# 05_Ethernet.net
KiCad netlist of a schematic drawn in Altium Designer
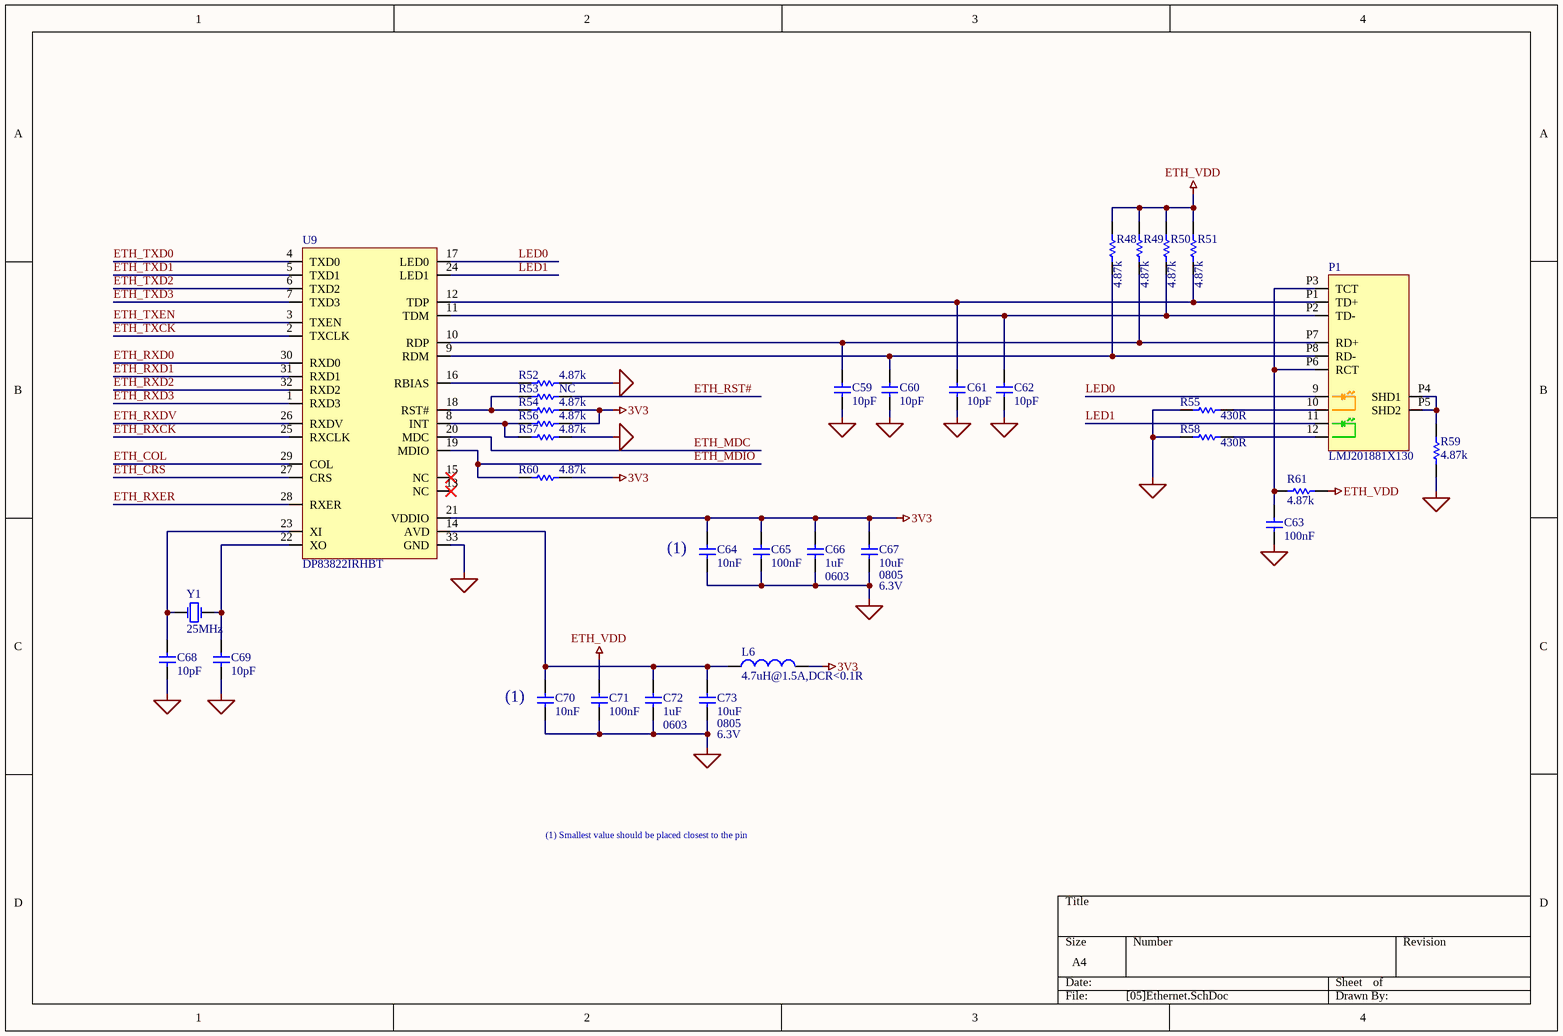
[diagram p0: [05]Ethernet.SchDoc]

(export (version "E")
  (design (tool "Eeschema 10.0.6"))
  (components
    (comp (ref "C59")
      (value "10pF")
      (footprint "C0402")
      (description "SMD Capacitor")
      (fields (field (name "MPN") "?") (field (name "TOLERANCE") "20%"))
      (libsource (lib "local") (part "CAP"))
    )
    (comp (ref "C60")
      (value "10pF")
      (footprint "C0402")
      (description "SMD Capacitor")
      (fields (field (name "MPN") "?") (field (name "TOLERANCE") "20%"))
      (libsource (lib "local") (part "CAP"))
    )
    (comp (ref "C61")
      (value "10pF")
      (footprint "C0402")
      (description "SMD Capacitor")
      (fields (field (name "MPN") "?") (field (name "TOLERANCE") "20%"))
      (libsource (lib "local") (part "CAP"))
    )
    (comp (ref "C62")
      (value "10pF")
      (footprint "C0402")
      (description "SMD Capacitor")
      (fields (field (name "MPN") "?") (field (name "TOLERANCE") "20%"))
      (libsource (lib "local") (part "CAP"))
    )
    (comp (ref "C63")
      (value "100nF")
      (footprint "C0402")
      (description "SMD Capacitor")
      (fields (field (name "MPN") "?") (field (name "TOLERANCE") "20%"))
      (libsource (lib "local") (part "CAP"))
    )
    (comp (ref "C64")
      (value "10nF")
      (footprint "C0402")
      (description "SMD Capacitor")
      (fields (field (name "MPN") "?") (field (name "TOLERANCE") "20%"))
      (libsource (lib "local") (part "CAP"))
    )
    (comp (ref "C65")
      (value "100nF")
      (footprint "C0402")
      (description "SMD Capacitor")
      (fields (field (name "MPN") "?") (field (name "TOLERANCE") "20%"))
      (libsource (lib "local") (part "CAP"))
    )
    (comp (ref "C66")
      (value "1uF")
      (footprint "C0603")
      (description "SMD Capacitor")
      (fields
        (field (name "MPN") "?")
        (field (name "TOLERANCE") "20%")
        (field (name "PACKAGE / CASE") "0603")
      )
      (libsource (lib "local") (part "CAP"))
    )
    (comp (ref "C67")
      (value "10uF")
      (footprint "C0805")
      (description "SMD Capacitor")
      (fields
        (field (name "MPN") "?")
        (field (name "TOLERANCE") "20%")
        (field (name "VOLTAGE") "6.3V")
        (field (name "PACKAGE / CASE") "0805")
      )
      (libsource (lib "local") (part "CAP"))
    )
    (comp (ref "C68")
      (value "10pF")
      (footprint "C0402")
      (description "SMD Capacitor")
      (fields (field (name "MPN") "?") (field (name "TOLERANCE") "20%"))
      (libsource (lib "local") (part "CAP"))
    )
    (comp (ref "C69")
      (value "10pF")
      (footprint "C0402")
      (description "SMD Capacitor")
      (fields (field (name "MPN") "?") (field (name "TOLERANCE") "20%"))
      (libsource (lib "local") (part "CAP"))
    )
    (comp (ref "C70")
      (value "10nF")
      (footprint "C0402")
      (description "SMD Capacitor")
      (fields (field (name "MPN") "?") (field (name "TOLERANCE") "20%"))
      (libsource (lib "local") (part "CAP"))
    )
    (comp (ref "C71")
      (value "100nF")
      (footprint "C0402")
      (description "SMD Capacitor")
      (fields (field (name "MPN") "?") (field (name "TOLERANCE") "20%"))
      (libsource (lib "local") (part "CAP"))
    )
    (comp (ref "C72")
      (value "1uF")
      (footprint "C0603")
      (description "SMD Capacitor")
      (fields
        (field (name "MPN") "?")
        (field (name "TOLERANCE") "20%")
        (field (name "PACKAGE / CASE") "0603")
      )
      (libsource (lib "local") (part "CAP"))
    )
    (comp (ref "C73")
      (value "10uF")
      (footprint "C0805")
      (description "SMD Capacitor")
      (fields
        (field (name "MPN") "?")
        (field (name "TOLERANCE") "20%")
        (field (name "VOLTAGE") "6.3V")
        (field (name "PACKAGE / CASE") "0805")
      )
      (libsource (lib "local") (part "CAP"))
    )
    (comp (ref "L6")
      (value "4.7uH@1.5A,DCR<0.1R")
      (description "SMD Coil")
      (fields (field (name "MPN") "?") (field (name "Comment") "SMD Coil Chip"))
      (libsource (lib "local") (part "COIL"))
    )
    (comp (ref "P1")
      (value "RJ45 Connector")
      (description "RJ45 Connector with Magnetics")
      (fields (field (name "MPN") "LMJ201881X130"))
      (libsource (lib "local") (part "RJ45"))
    )
    (comp (ref "R48")
      (value "4.87k")
      (description "SMD Resistor")
      (fields (field (name "MPN") "?") (field (name "TOLERANCE") "1%"))
      (libsource (lib "local") (part "RES"))
    )
    (comp (ref "R49")
      (value "4.87k")
      (description "SMD Resistor")
      (fields (field (name "MPN") "?") (field (name "TOLERANCE") "1%"))
      (libsource (lib "local") (part "RES"))
    )
    (comp (ref "R50")
      (value "4.87k")
      (description "SMD Resistor")
      (fields (field (name "MPN") "?") (field (name "TOLERANCE") "1%"))
      (libsource (lib "local") (part "RES"))
    )
    (comp (ref "R51")
      (value "4.87k")
      (description "SMD Resistor")
      (fields (field (name "MPN") "?") (field (name "TOLERANCE") "1%"))
      (libsource (lib "local") (part "RES"))
    )
    (comp (ref "R52")
      (value "4.87k")
      (description "SMD Resistor")
      (fields (field (name "MPN") "?") (field (name "TOLERANCE") "1%"))
      (libsource (lib "local") (part "RES"))
    )
    (comp (ref "R53")
      (value "NC")
      (description "SMD Resistor")
      (fields (field (name "MPN") "?") (field (name "TOLERANCE") "1%"))
      (libsource (lib "local") (part "RES"))
    )
    (comp (ref "R54")
      (value "4.87k")
      (description "SMD Resistor")
      (fields (field (name "MPN") "?") (field (name "TOLERANCE") "1%"))
      (libsource (lib "local") (part "RES"))
    )
    (comp (ref "R55")
      (value "430R")
      (description "SMD Resistor")
      (fields (field (name "MPN") "?") (field (name "TOLERANCE") "1%"))
      (libsource (lib "local") (part "RES"))
    )
    (comp (ref "R56")
      (value "4.87k")
      (description "SMD Resistor")
      (fields (field (name "MPN") "?") (field (name "TOLERANCE") "1%"))
      (libsource (lib "local") (part "RES"))
    )
    (comp (ref "R57")
      (value "4.87k")
      (description "SMD Resistor")
      (fields (field (name "MPN") "?") (field (name "TOLERANCE") "1%"))
      (libsource (lib "local") (part "RES"))
    )
    (comp (ref "R58")
      (value "430R")
      (description "SMD Resistor")
      (fields (field (name "MPN") "?") (field (name "TOLERANCE") "1%"))
      (libsource (lib "local") (part "RES"))
    )
    (comp (ref "R59")
      (value "4.87k")
      (description "SMD Resistor")
      (fields (field (name "MPN") "?") (field (name "TOLERANCE") "1%"))
      (libsource (lib "local") (part "RES"))
    )
    (comp (ref "R60")
      (value "4.87k")
      (description "SMD Resistor")
      (fields (field (name "MPN") "?") (field (name "TOLERANCE") "1%"))
      (libsource (lib "local") (part "RES"))
    )
    (comp (ref "R61")
      (value "4.87k")
      (description "SMD Resistor")
      (fields (field (name "MPN") "?") (field (name "TOLERANCE") "1%"))
      (libsource (lib "local") (part "RES"))
    )
    (comp (ref "U9")
      (value "SMD Ethernet PHY")
      (description "DP83822 Robust, Low Power 10/100 Mbps Ethernet Physical Layer Transceiver")
      (fields (field (name "MANUFACTURER") "Texas Instruments") (field (name "MPN") "DP83822IRHBT"))
      (libsource (lib "local") (part "DP83822"))
    )
    (comp (ref "Y1")
      (value "XTAL")
      (description "SMD Crystal Oscillator")
      (fields (field (name "MPN") "?") (field (name "FREQUENCY") "25MHz"))
      (libsource (lib "local") (part "XTAL"))
    )
  )
  (nets
    (net (code "1") (name "/ETH_COL") (class "Default")
      (node (ref "U9") (pin "29") (pinfunction "COL_29") (pintype "passive"))
    )
    (net (code "2") (name "/ETH_CRS") (class "Default")
      (node (ref "U9") (pin "27") (pinfunction "CRS_27") (pintype "passive"))
    )
    (net (code "3") (name "/ETH_MDC") (class "Default")
      (node (ref "U9") (pin "20") (pinfunction "MDC_20") (pintype "passive"))
    )
    (net (code "4") (name "/ETH_MDIO") (class "Default")
      (node (ref "R60") (pin "1") (pinfunction "1_1") (pintype "passive"))
      (node (ref "U9") (pin "19") (pinfunction "MDIO_19") (pintype "passive"))
    )
    (net (code "5") (name "/ETH_RST#") (class "Default")
      (node (ref "R53") (pin "2") (pinfunction "2_2") (pintype "passive"))
    )
    (net (code "6") (name "/ETH_RXCK") (class "Default")
      (node (ref "U9") (pin "25") (pinfunction "RXCLK_25") (pintype "passive"))
    )
    (net (code "7") (name "/ETH_RXD0") (class "Default")
      (node (ref "U9") (pin "30") (pinfunction "RXD0_30") (pintype "passive"))
    )
    (net (code "8") (name "/ETH_RXD1") (class "Default")
      (node (ref "U9") (pin "31") (pinfunction "RXD1_31") (pintype "passive"))
    )
    (net (code "9") (name "/ETH_RXD2") (class "Default")
      (node (ref "U9") (pin "32") (pinfunction "RXD2_32") (pintype "passive"))
    )
    (net (code "10") (name "/ETH_RXD3") (class "Default")
      (node (ref "U9") (pin "1") (pinfunction "RXD3_1") (pintype "passive"))
    )
    (net (code "11") (name "/ETH_RXDV") (class "Default")
      (node (ref "U9") (pin "26") (pinfunction "RXDV_26") (pintype "passive"))
    )
    (net (code "12") (name "/ETH_RXER") (class "Default")
      (node (ref "U9") (pin "28") (pinfunction "RXER_28") (pintype "passive"))
    )
    (net (code "13") (name "/ETH_TXCK") (class "Default")
      (node (ref "U9") (pin "2") (pinfunction "TXCLK_2") (pintype "passive"))
    )
    (net (code "14") (name "/ETH_TXD0") (class "Default")
      (node (ref "U9") (pin "4") (pinfunction "TXD0_4") (pintype "passive"))
    )
    (net (code "15") (name "/ETH_TXD1") (class "Default")
      (node (ref "U9") (pin "5") (pinfunction "TXD1_5") (pintype "passive"))
    )
    (net (code "16") (name "/ETH_TXD2") (class "Default")
      (node (ref "U9") (pin "6") (pinfunction "TXD2_6") (pintype "passive"))
    )
    (net (code "17") (name "/ETH_TXD3") (class "Default")
      (node (ref "U9") (pin "7") (pinfunction "TXD3_7") (pintype "passive"))
    )
    (net (code "18") (name "/ETH_TXEN") (class "Default")
      (node (ref "U9") (pin "3") (pinfunction "TXEN_3") (pintype "passive"))
    )
    (net (code "19") (name "/LED0") (class "Default")
      (node (ref "P1") (pin "9") (pinfunction "9_9") (pintype "passive"))
      (node (ref "U9") (pin "17") (pinfunction "LED0_17") (pintype "passive"))
    )
    (net (code "20") (name "/LED1") (class "Default")
      (node (ref "P1") (pin "11") (pinfunction "11_11") (pintype "passive"))
      (node (ref "U9") (pin "24") (pinfunction "LED1_24") (pintype "passive"))
    )
    (net (code "21") (name "3V3") (class "Default")
      (node (ref "C64") (pin "2") (pinfunction "2_2") (pintype "passive"))
      (node (ref "C65") (pin "2") (pinfunction "2_2") (pintype "passive"))
      (node (ref "C66") (pin "1") (pinfunction "1_1") (pintype "passive"))
      (node (ref "C67") (pin "1") (pinfunction "1_1") (pintype "passive"))
      (node (ref "L6") (pin "2") (pinfunction "2_2") (pintype "passive"))
      (node (ref "R54") (pin "2") (pinfunction "2_2") (pintype "passive"))
      (node (ref "R56") (pin "2") (pinfunction "2_2") (pintype "passive"))
      (node (ref "R60") (pin "2") (pinfunction "2_2") (pintype "passive"))
      (node (ref "U9") (pin "21") (pinfunction "VDDIO_21") (pintype "passive"))
    )
    (net (code "22") (name "ETH_VDD") (class "Default")
      (node (ref "C71") (pin "2") (pinfunction "2_2") (pintype "passive"))
      (node (ref "R48") (pin "2") (pinfunction "2_2") (pintype "passive"))
      (node (ref "R49") (pin "2") (pinfunction "2_2") (pintype "passive"))
      (node (ref "R50") (pin "2") (pinfunction "2_2") (pintype "passive"))
      (node (ref "R51") (pin "2") (pinfunction "2_2") (pintype "passive"))
      (node (ref "R61") (pin "1") (pinfunction "1_1") (pintype "passive"))
    )
    (net (code "23") (name "Net-(P1-Pad10)") (class "Default")
      (node (ref "P1") (pin "10") (pinfunction "10_10") (pintype "passive"))
      (node (ref "R55") (pin "1") (pinfunction "1_1") (pintype "passive"))
    )
    (net (code "24") (name "Net-(P1-Pad12)") (class "Default")
      (node (ref "P1") (pin "12") (pinfunction "12_12") (pintype "passive"))
      (node (ref "R58") (pin "1") (pinfunction "1_1") (pintype "passive"))
    )
    (net (code "25") (name "Net-(P1-RCT)") (class "Default")
      (node (ref "C63") (pin "2") (pinfunction "2_2") (pintype "passive"))
      (node (ref "P1") (pin "P3") (pinfunction "TCT_P3") (pintype "passive"))
      (node (ref "P1") (pin "P6") (pinfunction "RCT_P6") (pintype "passive"))
      (node (ref "R61") (pin "2") (pinfunction "2_2") (pintype "passive"))
    )
    (net (code "26") (name "Net-(P1-RD+)") (class "Default")
      (node (ref "C59") (pin "2") (pinfunction "2_2") (pintype "passive"))
      (node (ref "P1") (pin "P7") (pinfunction "RD+_P7") (pintype "passive"))
      (node (ref "R49") (pin "1") (pinfunction "1_1") (pintype "passive"))
      (node (ref "U9") (pin "10") (pinfunction "RDP_10") (pintype "passive"))
    )
    (net (code "27") (name "Net-(P1-RD-)") (class "Default")
      (node (ref "C60") (pin "2") (pinfunction "2_2") (pintype "passive"))
      (node (ref "P1") (pin "P8") (pinfunction "RD-_P8") (pintype "passive"))
      (node (ref "R48") (pin "1") (pinfunction "1_1") (pintype "passive"))
      (node (ref "U9") (pin "9") (pinfunction "RDM_9") (pintype "passive"))
    )
    (net (code "28") (name "Net-(P1-SHD1)") (class "Default")
      (node (ref "P1") (pin "P4") (pinfunction "SHD1_P4") (pintype "passive"))
      (node (ref "P1") (pin "P5") (pinfunction "SHD2_P5") (pintype "passive"))
      (node (ref "R59") (pin "1") (pinfunction "1_1") (pintype "passive"))
    )
    (net (code "29") (name "Net-(P1-TD+)") (class "Default")
      (node (ref "C61") (pin "2") (pinfunction "2_2") (pintype "passive"))
      (node (ref "P1") (pin "P1") (pinfunction "TD+_P1") (pintype "passive"))
      (node (ref "R51") (pin "1") (pinfunction "1_1") (pintype "passive"))
      (node (ref "U9") (pin "12") (pinfunction "TDP_12") (pintype "passive"))
    )
    (net (code "30") (name "Net-(P1-TD-)") (class "Default")
      (node (ref "C62") (pin "2") (pinfunction "2_2") (pintype "passive"))
      (node (ref "P1") (pin "P2") (pinfunction "TD-_P2") (pintype "passive"))
      (node (ref "R50") (pin "1") (pinfunction "1_1") (pintype "passive"))
      (node (ref "U9") (pin "11") (pinfunction "TDM_11") (pintype "passive"))
    )
    (net (code "31") (name "Net-(U9-AVD)") (class "Default")
      (node (ref "C70") (pin "2") (pinfunction "2_2") (pintype "passive"))
      (node (ref "C72") (pin "1") (pinfunction "1_1") (pintype "passive"))
      (node (ref "C73") (pin "1") (pinfunction "1_1") (pintype "passive"))
      (node (ref "L6") (pin "1") (pinfunction "1_1") (pintype "passive"))
      (node (ref "U9") (pin "14") (pinfunction "AVD_14") (pintype "passive"))
    )
    (net (code "32") (name "Net-(U9-INT)") (class "Default")
      (node (ref "R56") (pin "1") (pinfunction "1_1") (pintype "passive"))
      (node (ref "R57") (pin "1") (pinfunction "1_1") (pintype "passive"))
      (node (ref "U9") (pin "8") (pinfunction "INT_8") (pintype "passive"))
    )
    (net (code "33") (name "Net-(U9-RBIAS)") (class "Default")
      (node (ref "R52") (pin "1") (pinfunction "1_1") (pintype "passive"))
      (node (ref "U9") (pin "16") (pinfunction "RBIAS_16") (pintype "passive"))
    )
    (net (code "34") (name "Net-(U9-RST#)") (class "Default")
      (node (ref "R53") (pin "1") (pinfunction "1_1") (pintype "passive"))
      (node (ref "R54") (pin "1") (pinfunction "1_1") (pintype "passive"))
      (node (ref "U9") (pin "18") (pinfunction "RST#_18") (pintype "passive"))
    )
    (net (code "35") (name "Net-(U9-XI)") (class "Default")
      (node (ref "C68") (pin "1") (pinfunction "1_1") (pintype "passive"))
      (node (ref "U9") (pin "23") (pinfunction "XI_23") (pintype "passive"))
      (node (ref "Y1") (pin "2") (pinfunction "OSC2_2") (pintype "passive"))
    )
    (net (code "36") (name "Net-(U9-XO)") (class "Default")
      (node (ref "C69") (pin "1") (pinfunction "1_1") (pintype "passive"))
      (node (ref "U9") (pin "22") (pinfunction "XO_22") (pintype "passive"))
      (node (ref "Y1") (pin "1") (pinfunction "OSC1_1") (pintype "passive"))
    )
    (net (code "37") (name "SGND") (class "Default")
      (node (ref "C59") (pin "1") (pinfunction "1_1") (pintype "passive"))
      (node (ref "C60") (pin "1") (pinfunction "1_1") (pintype "passive"))
      (node (ref "C61") (pin "1") (pinfunction "1_1") (pintype "passive"))
      (node (ref "C62") (pin "1") (pinfunction "1_1") (pintype "passive"))
      (node (ref "C63") (pin "1") (pinfunction "1_1") (pintype "passive"))
      (node (ref "C64") (pin "1") (pinfunction "1_1") (pintype "passive"))
      (node (ref "C65") (pin "1") (pinfunction "1_1") (pintype "passive"))
      (node (ref "C66") (pin "2") (pinfunction "2_2") (pintype "passive"))
      (node (ref "C67") (pin "2") (pinfunction "2_2") (pintype "passive"))
      (node (ref "C68") (pin "2") (pinfunction "2_2") (pintype "passive"))
      (node (ref "C69") (pin "2") (pinfunction "2_2") (pintype "passive"))
      (node (ref "C70") (pin "1") (pinfunction "1_1") (pintype "passive"))
      (node (ref "C71") (pin "1") (pinfunction "1_1") (pintype "passive"))
      (node (ref "C72") (pin "2") (pinfunction "2_2") (pintype "passive"))
      (node (ref "C73") (pin "2") (pinfunction "2_2") (pintype "passive"))
      (node (ref "R52") (pin "2") (pinfunction "2_2") (pintype "passive"))
      (node (ref "R55") (pin "2") (pinfunction "2_2") (pintype "passive"))
      (node (ref "R57") (pin "2") (pinfunction "2_2") (pintype "passive"))
      (node (ref "R58") (pin "2") (pinfunction "2_2") (pintype "passive"))
      (node (ref "R59") (pin "2") (pinfunction "2_2") (pintype "passive"))
      (node (ref "U9") (pin "33") (pinfunction "GND_33") (pintype "passive"))
    )
    (net (code "38") (name "unconnected-(U9-NC-Pad13)") (class "Default")
      (node (ref "U9") (pin "13") (pinfunction "NC_13") (pintype "passive+no_connect"))
    )
    (net (code "39") (name "unconnected-(U9-NC-Pad15)") (class "Default")
      (node (ref "U9") (pin "15") (pinfunction "NC_15") (pintype "passive+no_connect"))
    )
  )
)
